# DC-DC_Circuit.net
KiCad netlist of a schematic drawn in Altium Designer
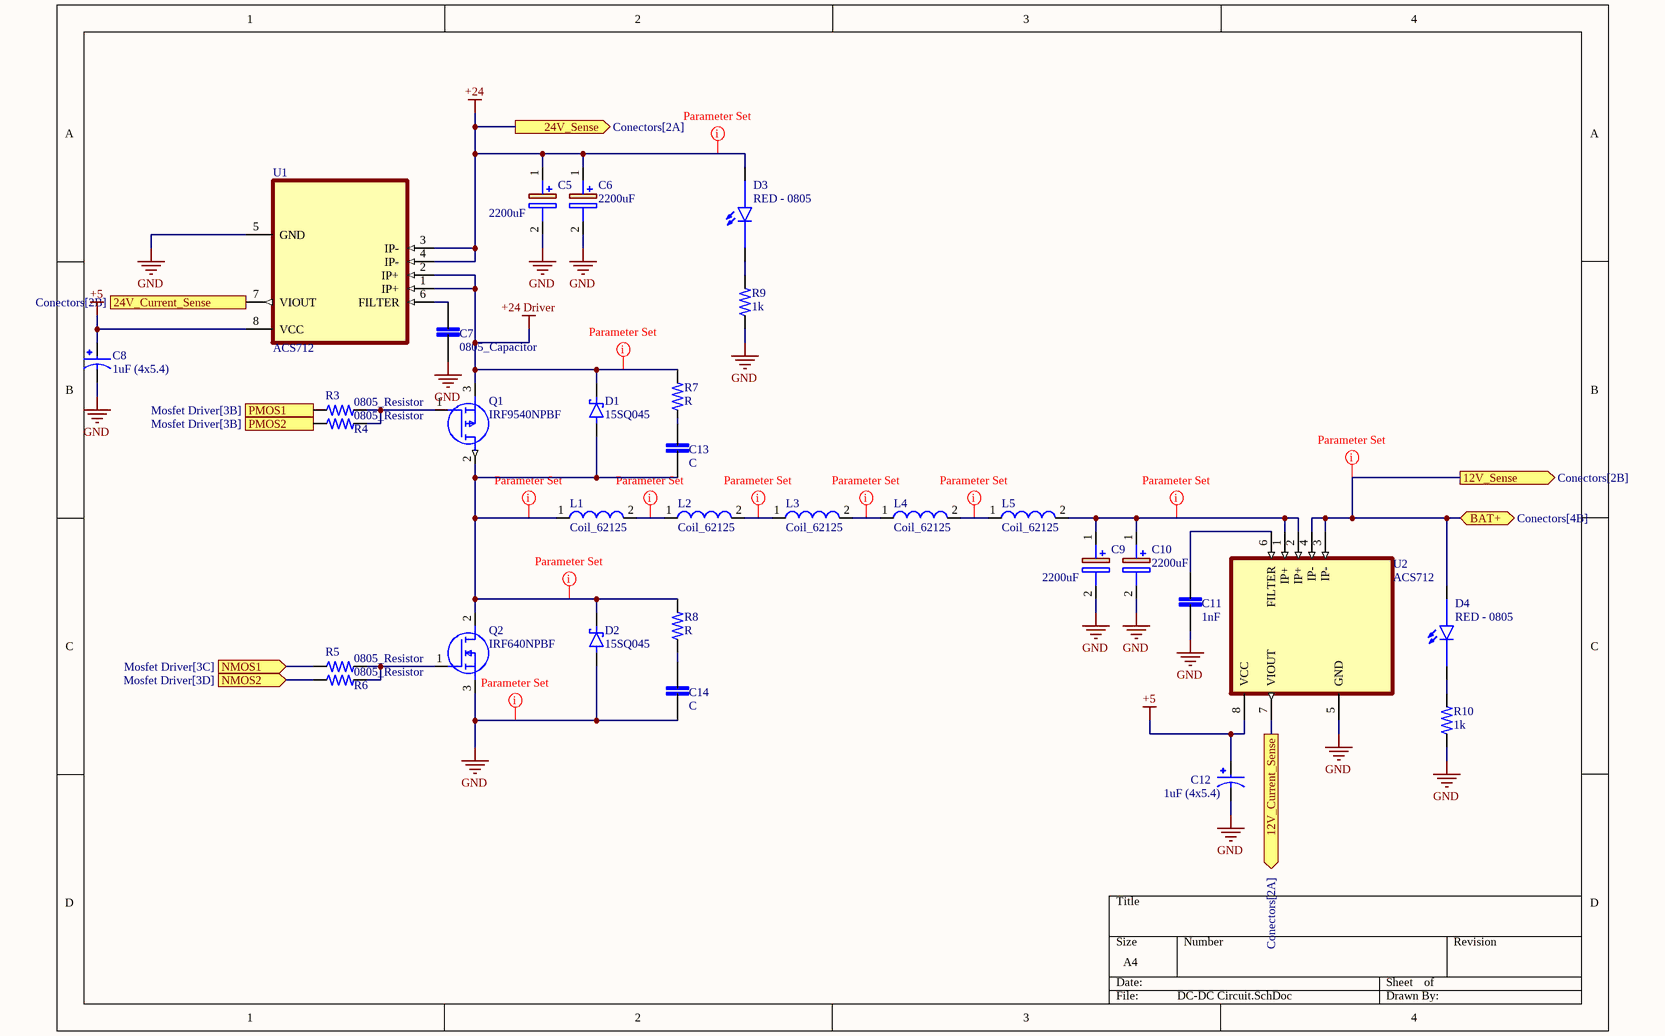
[diagram p0: DC-DC Circuit.SchDoc]

(export (version "E")
  (design (tool "Eeschema 10.0.6"))
  (components
    (comp (ref "C5")
      (value "2200uF")
      (footprint "SamacSys:CAPPRD500W62D1300H2150")
      (description "Capacitor Polarised")
      (fields
        (field (name "MANUFACTURER_PART_NUMBER") "860020578018")
        (field (name "MOUSER PART NUMBER") "710-860020578018")
      )
      (libsource (lib "*") (part "860020578018"))
    )
    (comp (ref "C6")
      (value "2200uF")
      (footprint "SamacSys:CAPPRD500W62D1300H2150")
      (description "Capacitor Polarised")
      (fields
        (field (name "MANUFACTURER_PART_NUMBER") "860020578018")
        (field (name "MOUSER PART NUMBER") "710-860020578018")
      )
      (libsource (lib "*") (part "860020578018"))
    )
    (comp (ref "C7")
      (value "0805_Capacitor")
      (footprint "0805")
      (fields (field (name "MP") "LD051A121KAB2A") (field (name "MF") "AVX"))
      (libsource (lib "") (part "0805_Capacitor_1"))
    )
    (comp (ref "C8")
      (value "1uF (4x5.4)")
      (footprint "Capacitors SMD:Electrolytic 4x5.4")
      (fields (field (name "MF") "Panasonic") (field (name "MP") "EEE-HA1E100WR"))
      (libsource (lib "Capacitors SMD") (part "Electrolytic 4x5.4"))
    )
    (comp (ref "C9")
      (value "2200uF")
      (footprint "SamacSys:CAPPRD500W62D1300H2150")
      (description "Capacitor Polarised")
      (fields
        (field (name "MANUFACTURER_PART_NUMBER") "860020578018")
        (field (name "MOUSER PART NUMBER") "710-860020578018")
      )
      (libsource (lib "*") (part "860020578018"))
    )
    (comp (ref "C10")
      (value "2200uF")
      (footprint "SamacSys:CAPPRD500W62D1300H2150")
      (description "Capacitor Polarised")
      (fields
        (field (name "MANUFACTURER_PART_NUMBER") "860020578018")
        (field (name "MOUSER PART NUMBER") "710-860020578018")
      )
      (libsource (lib "*") (part "860020578018"))
    )
    (comp (ref "C11")
      (value "1nF")
      (footprint "0805")
      (fields (field (name "MP") "LD051A121KAB2A") (field (name "MF") "AVX"))
      (libsource (lib "") (part "0805_Capacitor_1"))
    )
    (comp (ref "C12")
      (value "1uF (4x5.4)")
      (footprint "Capacitors SMD:Electrolytic 4x5.4")
      (fields (field (name "MF") "Panasonic") (field (name "MP") "EEE-HA1E100WR"))
      (libsource (lib "Capacitors SMD") (part "Electrolytic 4x5.4"))
    )
    (comp (ref "C13")
      (value "C")
      (footprint "0805")
      (fields (field (name "MP") "LD051A121KAB2A") (field (name "MF") "AVX"))
      (libsource (lib "Capacitors SMD") (part "0805_Capacitor"))
    )
    (comp (ref "C14")
      (value "C")
      (footprint "0805")
      (fields (field (name "MP") "LD051A121KAB2A") (field (name "MF") "AVX"))
      (libsource (lib "Capacitors SMD") (part "0805_Capacitor"))
    )
    (comp (ref "D1")
      (value "15SQ045")
      (footprint "Common Trhough Hole")
      (fields (field (name "MF") "Diodes Inc.") (field (name "MP") "1N5817-T"))
      (libsource (lib "Diodes Through Hole") (part "Schottky Diode"))
    )
    (comp (ref "D2")
      (value "15SQ045")
      (footprint "Common Trhough Hole")
      (fields (field (name "MF") "Diodes Inc.") (field (name "MP") "1N5817-T"))
      (libsource (lib "Diodes Through Hole") (part "Schottky Diode"))
    )
    (comp (ref "D3")
      (value "RED - 0805")
      (footprint "LED 0805")
      (description "LED Uni-Color Green 4-Pin Chip 0805 T/R")
      (fields (field (name "MP") "597-3305-607F"))
      (libsource (lib "LEDs SMD") (part "LED 0805"))
    )
    (comp (ref "D4")
      (value "RED - 0805")
      (footprint "LED 0805")
      (description "LED Uni-Color Green 4-Pin Chip 0805 T/R")
      (fields (field (name "MP") "597-3305-607F"))
      (libsource (lib "LEDs SMD") (part "LED 0805"))
    )
    (comp (ref "L1")
      (value "Coil_62125")
      (footprint "Coil 65125")
      (description "Inductor Power Wirewound 470uH 10% 1KHz 25Q-Factor Ferrite 210mA 3.3Ohm DCR T/R")
      (fields (field (name "DIGI-KEY_PART_NUMBER") "SDR0604-471KLCT-ND") (field (name "MF") "Bourns"))
      (libsource (lib "MySCH_Library") (part "Coil_62125"))
    )
    (comp (ref "L2")
      (value "Coil_62125")
      (footprint "Coil 65125")
      (description "Inductor Power Wirewound 470uH 10% 1KHz 25Q-Factor Ferrite 210mA 3.3Ohm DCR T/R")
      (fields (field (name "DIGI-KEY_PART_NUMBER") "SDR0604-471KLCT-ND") (field (name "MF") "Bourns"))
      (libsource (lib "MySCH_Library") (part "Coil_62125"))
    )
    (comp (ref "L3")
      (value "Coil_62125")
      (footprint "Coil 65125")
      (description "Inductor Power Wirewound 470uH 10% 1KHz 25Q-Factor Ferrite 210mA 3.3Ohm DCR T/R")
      (fields (field (name "DIGI-KEY_PART_NUMBER") "SDR0604-471KLCT-ND") (field (name "MF") "Bourns"))
      (libsource (lib "MySCH_Library") (part "Coil_62125"))
    )
    (comp (ref "L4")
      (value "Coil_62125")
      (footprint "Coil 65125")
      (description "Inductor Power Wirewound 470uH 10% 1KHz 25Q-Factor Ferrite 210mA 3.3Ohm DCR T/R")
      (fields (field (name "DIGI-KEY_PART_NUMBER") "SDR0604-471KLCT-ND") (field (name "MF") "Bourns"))
      (libsource (lib "MySCH_Library") (part "Coil_62125"))
    )
    (comp (ref "L5")
      (value "Coil_62125")
      (footprint "Coil 65125")
      (description "Inductor Power Wirewound 470uH 10% 1KHz 25Q-Factor Ferrite 210mA 3.3Ohm DCR T/R")
      (fields (field (name "DIGI-KEY_PART_NUMBER") "SDR0604-471KLCT-ND") (field (name "MF") "Bourns"))
      (libsource (lib "MySCH_Library") (part "Coil_62125"))
    )
    (comp (ref "Q1")
      (value "IRF9540NPBF")
      (footprint "SamacSys:TO254P469X1042X1967-3P")
      (description "MOSFET (P-Channel)")
      (fields (field (name "MOUSER PART NUMBER") "942-IRF9540NPBF"))
      (libsource (lib "*") (part "IRF9540NPBF"))
    )
    (comp (ref "Q2")
      (value "IRF640NPBF")
      (footprint "SamacSys:TO254P483X1016X1994-3P")
      (description "MOSFET (N-Channel)")
      (fields (field (name "MOUSER PART NUMBER") "942-IRF640NPBF"))
      (libsource (lib "*") (part "IRF640NPBF"))
    )
    (comp (ref "R3")
      (value "0805_Resistor")
      (footprint "0805")
      (fields
        (field (name "MP") "2-2176053-0")
        (field (name "TOLERANCE") "1%")
        (field (name "MF") "TE Connectivity")
      )
      (libsource (lib "Resistors SMD") (part "0805_Resistor"))
    )
    (comp (ref "R4")
      (value "0805_Resistor")
      (footprint "0805")
      (fields
        (field (name "MP") "2-2176053-0")
        (field (name "TOLERANCE") "1%")
        (field (name "MF") "TE Connectivity")
      )
      (libsource (lib "Resistors SMD") (part "0805_Resistor"))
    )
    (comp (ref "R5")
      (value "0805_Resistor")
      (footprint "0805")
      (fields
        (field (name "MP") "2-2176053-0")
        (field (name "TOLERANCE") "1%")
        (field (name "MF") "TE Connectivity")
      )
      (libsource (lib "Resistors SMD") (part "0805_Resistor"))
    )
    (comp (ref "R6")
      (value "0805_Resistor")
      (footprint "0805")
      (fields
        (field (name "MP") "2-2176053-0")
        (field (name "TOLERANCE") "1%")
        (field (name "MF") "TE Connectivity")
      )
      (libsource (lib "Resistors SMD") (part "0805_Resistor"))
    )
    (comp (ref "R7")
      (value "R")
      (footprint "0805")
      (fields
        (field (name "MP") "2-2176053-0")
        (field (name "TOLERANCE") "1%")
        (field (name "MF") "TE Connectivity")
      )
      (libsource (lib "Resistors SMD") (part "0805_Resistor"))
    )
    (comp (ref "R8")
      (value "R")
      (footprint "0805")
      (fields
        (field (name "MP") "2-2176053-0")
        (field (name "TOLERANCE") "1%")
        (field (name "MF") "TE Connectivity")
      )
      (libsource (lib "Resistors SMD") (part "0805_Resistor"))
    )
    (comp (ref "R9")
      (value "1k")
      (footprint "0805")
      (fields
        (field (name "MP") "2-2176053-0")
        (field (name "TOLERANCE") "1%")
        (field (name "MF") "TE Connectivity")
      )
      (libsource (lib "Resistors SMD") (part "0805_Resistor"))
    )
    (comp (ref "R10")
      (value "1k")
      (footprint "0805")
      (fields
        (field (name "MP") "2-2176053-0")
        (field (name "TOLERANCE") "1%")
        (field (name "MF") "TE Connectivity")
      )
      (libsource (lib "Resistors SMD") (part "0805_Resistor"))
    )
    (comp (ref "U1")
      (value "ACS712")
      (footprint "ACS712")
      (description "Current Sensor 5A 1 Channel Hall Effect, Open Loop Bidirectional 8-SOIC (0.154, 3.90mm Width)")
      (fields (field (name "MP") "ACS712ELCTR-05B-T") (field (name "MF") "Allegro MicroSystems LLC"))
      (libsource (lib "Hall Current Sensor") (part "ACS712"))
    )
    (comp (ref "U2")
      (value "ACS712")
      (footprint "ACS712")
      (description "Current Sensor 5A 1 Channel Hall Effect, Open Loop Bidirectional 8-SOIC (0.154, 3.90mm Width)")
      (fields (field (name "MP") "ACS712ELCTR-05B-T") (field (name "MF") "Allegro MicroSystems LLC"))
      (libsource (lib "Hall Current Sensor") (part "ACS712"))
    )
  )
  (nets
    (net (code "1") (name "+5") (class "Default")
      (node (ref "C12") (pin "1") (pinfunction "1_1") (pintype "passive"))
      (node (ref "C8") (pin "1") (pinfunction "1_1") (pintype "passive"))
      (node (ref "U1") (pin "8") (pinfunction "VCC_8") (pintype "power_in"))
      (node (ref "U2") (pin "8") (pinfunction "VCC_8") (pintype "power_in"))
    )
    (net (code "2") (name "+24") (class "Default")
      (node (ref "C5") (pin "1") (pinfunction "+_1") (pintype "power_in"))
      (node (ref "C6") (pin "1") (pinfunction "+_1") (pintype "power_in"))
      (node (ref "D3") (pin "A") (pinfunction "A_A") (pintype "passive"))
      (node (ref "U1") (pin "3") (pinfunction "IP-_3") (pintype "input"))
      (node (ref "U1") (pin "4") (pinfunction "IP-_4") (pintype "input"))
    )
    (net (code "3") (name "+24 Driver") (class "Default")
      (node (ref "D1") (pin "1") (pinfunction "K_1") (pintype "passive"))
      (node (ref "Q1") (pin "3") (pinfunction "S_3") (pintype "power_in"))
      (node (ref "R7") (pin "2") (pinfunction "2_2") (pintype "passive"))
      (node (ref "U1") (pin "1") (pinfunction "IP+_1") (pintype "input"))
      (node (ref "U1") (pin "2") (pinfunction "IP+_2") (pintype "input"))
    )
    (net (code "4") (name "/12V_Current_Sense") (class "Default")
      (node (ref "U2") (pin "7") (pinfunction "VIOUT_7") (pintype "output"))
    )
    (net (code "5") (name "/12V_Sense") (class "Default")
      (node (ref "D4") (pin "A") (pinfunction "A_A") (pintype "passive"))
      (node (ref "U2") (pin "3") (pinfunction "IP-_3") (pintype "input"))
      (node (ref "U2") (pin "4") (pinfunction "IP-_4") (pintype "input"))
    )
    (net (code "6") (name "/24V_Current_Sense") (class "Default")
      (node (ref "U1") (pin "7") (pinfunction "VIOUT_7") (pintype "output"))
    )
    (net (code "7") (name "/NMOS1") (class "Default")
      (node (ref "R5") (pin "1") (pinfunction "1_1") (pintype "passive"))
    )
    (net (code "8") (name "/NMOS2") (class "Default")
      (node (ref "R6") (pin "1") (pinfunction "1_1") (pintype "passive"))
    )
    (net (code "9") (name "/PMOS1") (class "Default")
      (node (ref "R3") (pin "1") (pinfunction "1_1") (pintype "passive"))
    )
    (net (code "10") (name "/PMOS2") (class "Default")
      (node (ref "R4") (pin "1") (pinfunction "1_1") (pintype "passive"))
    )
    (net (code "11") (name "GND") (class "Default")
      (node (ref "C10") (pin "2") (pinfunction "-_2") (pintype "power_in"))
      (node (ref "C11") (pin "1") (pinfunction "1_1") (pintype "passive"))
      (node (ref "C12") (pin "2") (pinfunction "2_2") (pintype "passive"))
      (node (ref "C14") (pin "2") (pinfunction "2_2") (pintype "passive"))
      (node (ref "C5") (pin "2") (pinfunction "-_2") (pintype "power_in"))
      (node (ref "C6") (pin "2") (pinfunction "-_2") (pintype "power_in"))
      (node (ref "C7") (pin "1") (pinfunction "1_1") (pintype "passive"))
      (node (ref "C8") (pin "2") (pinfunction "2_2") (pintype "passive"))
      (node (ref "C9") (pin "2") (pinfunction "-_2") (pintype "power_in"))
      (node (ref "D2") (pin "2") (pinfunction "A_2") (pintype "passive"))
      (node (ref "Q2") (pin "3") (pinfunction "S_3") (pintype "passive"))
      (node (ref "R10") (pin "1") (pinfunction "1_1") (pintype "passive"))
      (node (ref "R9") (pin "1") (pinfunction "1_1") (pintype "passive"))
      (node (ref "U1") (pin "5") (pinfunction "GND_5") (pintype "power_in"))
      (node (ref "U2") (pin "5") (pinfunction "GND_5") (pintype "power_in"))
    )
    (net (code "12") (name "Net-(C10-+)") (class "Default")
      (node (ref "C10") (pin "1") (pinfunction "+_1") (pintype "power_in"))
      (node (ref "C9") (pin "1") (pinfunction "+_1") (pintype "power_in"))
      (node (ref "L5") (pin "2") (pinfunction "2_2") (pintype "passive"))
      (node (ref "U2") (pin "1") (pinfunction "IP+_1") (pintype "input"))
      (node (ref "U2") (pin "2") (pinfunction "IP+_2") (pintype "input"))
    )
    (net (code "13") (name "Net-(C13-Pad1)") (class "Default")
      (node (ref "C13") (pin "1") (pinfunction "1_1") (pintype "passive"))
      (node (ref "R7") (pin "1") (pinfunction "1_1") (pintype "passive"))
    )
    (net (code "14") (name "Net-(C14-Pad1)") (class "Default")
      (node (ref "C14") (pin "1") (pinfunction "1_1") (pintype "passive"))
      (node (ref "R8") (pin "1") (pinfunction "1_1") (pintype "passive"))
    )
    (net (code "15") (name "Net-(D1-A)") (class "Default")
      (node (ref "C13") (pin "2") (pinfunction "2_2") (pintype "passive"))
      (node (ref "D1") (pin "2") (pinfunction "A_2") (pintype "passive"))
      (node (ref "D2") (pin "1") (pinfunction "K_1") (pintype "passive"))
      (node (ref "L1") (pin "1") (pinfunction "1_1") (pintype "passive"))
      (node (ref "Q1") (pin "2") (pinfunction "D_2") (pintype "output"))
      (node (ref "Q2") (pin "2") (pinfunction "D_2") (pintype "passive"))
      (node (ref "R8") (pin "2") (pinfunction "2_2") (pintype "passive"))
    )
    (net (code "16") (name "Net-(D3-PadC)") (class "Default")
      (node (ref "D3") (pin "C") (pinfunction "C_C") (pintype "passive"))
      (node (ref "R9") (pin "2") (pinfunction "2_2") (pintype "passive"))
    )
    (net (code "17") (name "Net-(D4-PadC)") (class "Default")
      (node (ref "D4") (pin "C") (pinfunction "C_C") (pintype "passive"))
      (node (ref "R10") (pin "2") (pinfunction "2_2") (pintype "passive"))
    )
    (net (code "18") (name "Net-(L1-Pad2)") (class "Default")
      (node (ref "L1") (pin "2") (pinfunction "2_2") (pintype "passive"))
      (node (ref "L2") (pin "1") (pinfunction "1_1") (pintype "passive"))
    )
    (net (code "19") (name "Net-(L2-Pad2)") (class "Default")
      (node (ref "L2") (pin "2") (pinfunction "2_2") (pintype "passive"))
      (node (ref "L3") (pin "1") (pinfunction "1_1") (pintype "passive"))
    )
    (net (code "20") (name "Net-(L3-Pad2)") (class "Default")
      (node (ref "L3") (pin "2") (pinfunction "2_2") (pintype "passive"))
      (node (ref "L4") (pin "1") (pinfunction "1_1") (pintype "passive"))
    )
    (net (code "21") (name "Net-(L4-Pad2)") (class "Default")
      (node (ref "L4") (pin "2") (pinfunction "2_2") (pintype "passive"))
      (node (ref "L5") (pin "1") (pinfunction "1_1") (pintype "passive"))
    )
    (net (code "22") (name "Net-(Q1-G)") (class "Default")
      (node (ref "Q1") (pin "1") (pinfunction "G_1") (pintype "power_in"))
      (node (ref "R3") (pin "2") (pinfunction "2_2") (pintype "passive"))
      (node (ref "R4") (pin "2") (pinfunction "2_2") (pintype "passive"))
    )
    (net (code "23") (name "Net-(Q2-G)") (class "Default")
      (node (ref "Q2") (pin "1") (pinfunction "G_1") (pintype "passive"))
      (node (ref "R5") (pin "2") (pinfunction "2_2") (pintype "passive"))
      (node (ref "R6") (pin "2") (pinfunction "2_2") (pintype "passive"))
    )
    (net (code "24") (name "Net-(U1-FILTER)") (class "Default")
      (node (ref "C7") (pin "2") (pinfunction "2_2") (pintype "passive"))
      (node (ref "U1") (pin "6") (pinfunction "FILTER_6") (pintype "input"))
    )
    (net (code "25") (name "Net-(U2-FILTER)") (class "Default")
      (node (ref "C11") (pin "2") (pinfunction "2_2") (pintype "passive"))
      (node (ref "U2") (pin "6") (pinfunction "FILTER_6") (pintype "input"))
    )
  )
)
